# Cpu.net
KiCad netlist of a schematic drawn in Altium Designer
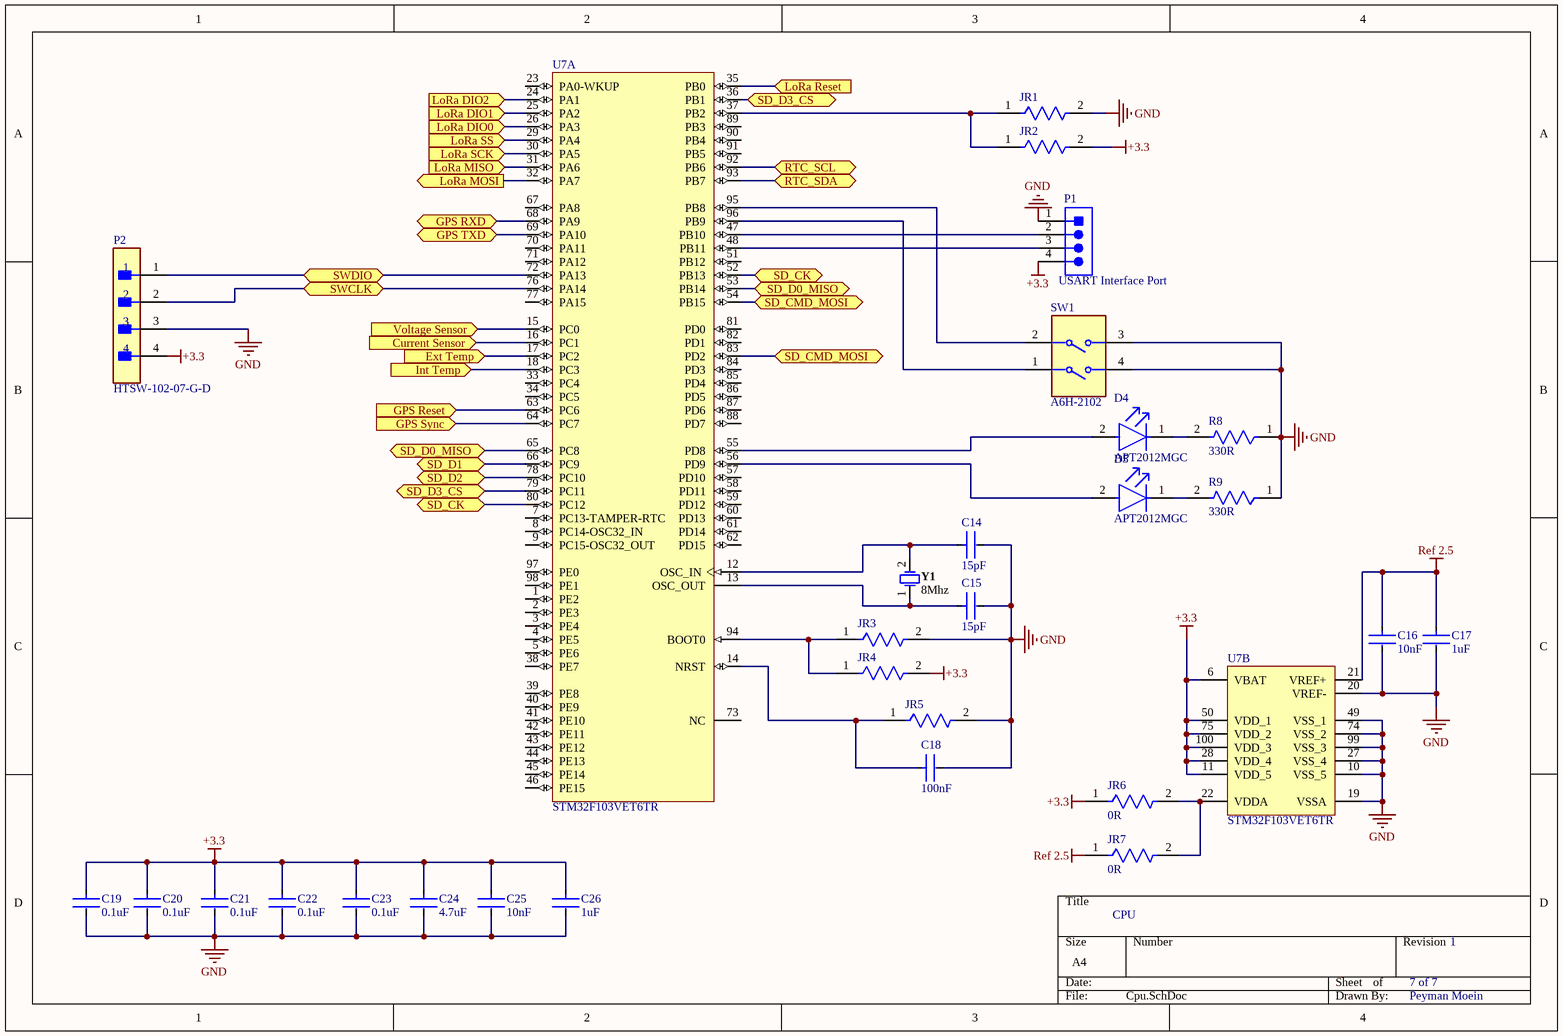
[diagram p0: Cpu.SchDoc]

(export (version "E")
  (design (tool "Eeschema 10.0.6"))
  (components
    (comp (ref "C14")
      (value "15pF")
      (footprint "FP-C0805C-DN-MFG")
      (description "C396747")
      (fields
        (field (name "MANUFACTURER PART NUMBER") "C0805C104K5RACTU")
        (field (name "MANUFACTURER") "KEMET")
      )
      (libsource (lib "Altium Content Vault") (part "b4654b650e69147ec39a6b967a45e02"))
    )
    (comp (ref "C15")
      (value "15pF")
      (footprint "FP-C0805C-DN-MFG")
      (description "C396747")
      (fields
        (field (name "MANUFACTURER PART NUMBER") "C0805C104K5RACTU")
        (field (name "MANUFACTURER") "KEMET")
      )
      (libsource (lib "Altium Content Vault") (part "b4654b650e69147ec39a6b967a45e02"))
    )
    (comp (ref "C16")
      (value "10nF")
      (footprint "FP-C0805C-DN-MFG")
      (description "C188188")
      (fields
        (field (name "MANUFACTURER PART NUMBER") "C0805C104K5RACTU")
        (field (name "MANUFACTURER") "KEMET")
      )
      (libsource (lib "Altium Content Vault") (part "b4654b650e69147ec39a6b967a45e02"))
    )
    (comp (ref "C17")
      (value "1uF")
      (footprint "FP-C0805C-DN-MFG")
      (description "C89190")
      (fields
        (field (name "MANUFACTURER PART NUMBER") "C0805C104K5RACTU")
        (field (name "MANUFACTURER") "KEMET")
      )
      (libsource (lib "Altium Content Vault") (part "b4654b650e69147ec39a6b967a45e02"))
    )
    (comp (ref "C18")
      (value "100nF")
      (footprint "FP-C0805C-DN-MFG")
      (description "C49678")
      (fields
        (field (name "MANUFACTURER PART NUMBER") "C0805C104K5RACTU")
        (field (name "MANUFACTURER") "KEMET")
      )
      (libsource (lib "Altium Content Vault") (part "b4654b650e69147ec39a6b967a45e02"))
    )
    (comp (ref "C19")
      (value "0.1uF")
      (footprint "FP-C0805C-DN-MFG")
      (description "C49678")
      (fields
        (field (name "MANUFACTURER PART NUMBER") "C0805C104K5RACTU")
        (field (name "MANUFACTURER") "KEMET")
      )
      (libsource (lib "Altium Content Vault") (part "b4654b650e69147ec39a6b967a45e02"))
    )
    (comp (ref "C20")
      (value "0.1uF")
      (footprint "FP-C0805C-DN-MFG")
      (description "C49678")
      (fields
        (field (name "MANUFACTURER PART NUMBER") "C0805C104K5RACTU")
        (field (name "MANUFACTURER") "KEMET")
      )
      (libsource (lib "Altium Content Vault") (part "b4654b650e69147ec39a6b967a45e02"))
    )
    (comp (ref "C21")
      (value "0.1uF")
      (footprint "FP-C0805C-DN-MFG")
      (description "C49678")
      (fields
        (field (name "MANUFACTURER PART NUMBER") "C0805C104K5RACTU")
        (field (name "MANUFACTURER") "KEMET")
      )
      (libsource (lib "Altium Content Vault") (part "b4654b650e69147ec39a6b967a45e02"))
    )
    (comp (ref "C22")
      (value "0.1uF")
      (footprint "FP-C0805C-DN-MFG")
      (description "C49678")
      (fields
        (field (name "MANUFACTURER PART NUMBER") "C0805C104K5RACTU")
        (field (name "MANUFACTURER") "KEMET")
      )
      (libsource (lib "Altium Content Vault") (part "b4654b650e69147ec39a6b967a45e02"))
    )
    (comp (ref "C23")
      (value "0.1uF")
      (footprint "FP-C0805C-DN-MFG")
      (description "C49678")
      (fields
        (field (name "MANUFACTURER PART NUMBER") "C0805C104K5RACTU")
        (field (name "MANUFACTURER") "KEMET")
      )
      (libsource (lib "Altium Content Vault") (part "b4654b650e69147ec39a6b967a45e02"))
    )
    (comp (ref "C24")
      (value "4.7uF")
      (footprint "FP-C0805C-DN-MFG")
      (description "C215908")
      (fields
        (field (name "MANUFACTURER PART NUMBER") "C0805C104K5RACTU")
        (field (name "MANUFACTURER") "KEMET")
      )
      (libsource (lib "Altium Content Vault") (part "b4654b650e69147ec39a6b967a45e02"))
    )
    (comp (ref "C25")
      (value "10nF")
      (footprint "FP-C0805C-DN-MFG")
      (description "C188188")
      (fields
        (field (name "MANUFACTURER PART NUMBER") "C0805C104K5RACTU")
        (field (name "MANUFACTURER") "KEMET")
      )
      (libsource (lib "Altium Content Vault") (part "b4654b650e69147ec39a6b967a45e02"))
    )
    (comp (ref "C26")
      (value "1uF")
      (footprint "FP-C0805C-DN-MFG")
      (description "C89190")
      (fields
        (field (name "MANUFACTURER PART NUMBER") "C0805C104K5RACTU")
        (field (name "MANUFACTURER") "KEMET")
      )
      (libsource (lib "Altium Content Vault") (part "b4654b650e69147ec39a6b967a45e02"))
    )
    (comp (ref "D4")
      (value "APT2012MGC")
      (footprint "FP-APT2012MGC-MFG")
      (description "C434432")
      (libsource (lib "Altium Content Vault") (part "8706943c75ba83719d021d2fdc84c58"))
    )
    (comp (ref "D5")
      (value "APT2012MGC")
      (footprint "FP-APT2012MGC-MFG")
      (description "C434432")
      (libsource (lib "Altium Content Vault") (part "8706943c75ba83719d021d2fdc84c58"))
    )
    (comp (ref "JR1")
      (value "0R")
      (footprint "FP-RMCF0805-MFG")
      (description "RES 0 OHM JUMPER 1/8W 0805")
      (libsource (lib "Altium Content Vault") (part "1029c3af85768c4190bb7ad29bc67b5"))
    )
    (comp (ref "JR2")
      (value "0R")
      (footprint "FP-RMCF0805-MFG")
      (libsource (lib "Altium Content Vault") (part "1029c3af85768c4190bb7ad29bc67b5"))
    )
    (comp (ref "JR3")
      (value "0R")
      (footprint "FP-RMCF0805-MFG")
      (description "C25275")
      (libsource (lib "Altium Content Vault") (part "1029c3af85768c4190bb7ad29bc67b5"))
    )
    (comp (ref "JR4")
      (value "0R")
      (footprint "FP-RMCF0805-MFG")
      (description "RES 0 OHM JUMPER 1/8W 0805")
      (libsource (lib "Altium Content Vault") (part "1029c3af85768c4190bb7ad29bc67b5"))
    )
    (comp (ref "JR5")
      (value "NC")
      (footprint "FP-RMCF0805-MFG")
      (description "RES 0 OHM JUMPER 1/8W 0805")
      (libsource (lib "Altium Content Vault") (part "1029c3af85768c4190bb7ad29bc67b5"))
    )
    (comp (ref "JR6")
      (value "0R")
      (footprint "FP-RMCF0805-MFG")
      (description "RES 0 OHM JUMPER 1/8W 0805")
      (libsource (lib "Altium Content Vault") (part "1029c3af85768c4190bb7ad29bc67b5"))
    )
    (comp (ref "JR7")
      (value "0R")
      (footprint "FP-RMCF0805-MFG")
      (description "C25275")
      (libsource (lib "Altium Content Vault") (part "1029c3af85768c4190bb7ad29bc67b5"))
    )
    (comp (ref "P1")
      (value "USART Interface Port")
      (footprint "JST-S4B-XH-A(LF)(SN)_V")
      (description "C157925")
      (libsource (lib "Altium Content Vault") (part "CN-1P-M-R4"))
    )
    (comp (ref "P2")
      (value "HTSW-102-07-G-D")
      (footprint "FP-HTSW-102-07-G-D-MFG")
      (description "C66690")
      (fields
        (field (name "MANUFACTURER") "Samtec")
        (field (name "OCTOPART") "https://octopart.com/htsw-102-07-g-d-samtec-10531767")
      )
      (libsource (lib "Altium Content Vault") (part "299a8cea1bdcbc3624fe62c390fa72c"))
    )
    (comp (ref "R8")
      (value "330R")
      (footprint "FP-CRCW0805-e3-MFG")
      (description "C17630")
      (fields (field (name "TOLERANCE") "1%"))
      (libsource (lib "Altium Content Vault") (part "1029c3af85768c4190bb7ad29bc67b5"))
    )
    (comp (ref "R9")
      (value "330R")
      (footprint "FP-CRCW0805-e3-MFG")
      (description "C17630")
      (fields (field (name "TOLERANCE") "1%"))
      (libsource (lib "Altium Content Vault") (part "1029c3af85768c4190bb7ad29bc67b5"))
    )
    (comp (ref "SW1")
      (value "A6H-2102")
      (footprint "FP-A6H-2102-MFG")
      (description "SWITCH SLIDE DIP SPST 25MA 24V")
      (libsource (lib "Altium Content Vault") (part "070a973bb9dfaf4112c7cb8da95b8f6"))
    )
    (comp (ref "U7")
      (value "STM32F103VET6TR")
      (footprint "STM-LQFP100_L")
      (description "C8308")
      (libsource (lib "Altium Content Vault") (part "MC-ARM-STM32F103XC_D_E-SQ100"))
    )
    (comp (ref "Y1")
      (value "8Mhz")
      (footprint "FOX-FOXSLF080-20")
      (description "C111806")
      (libsource (lib "Altium Content Vault") (part "XTAL-1-2-2"))
    )
  )
  (nets
    (net (code "1") (name "+3.3") (class "Default")
      (node (ref "C19") (pin "1") (pinfunction "1_1") (pintype "passive"))
      (node (ref "C20") (pin "1") (pinfunction "1_1") (pintype "passive"))
      (node (ref "C21") (pin "1") (pinfunction "1_1") (pintype "passive"))
      (node (ref "C22") (pin "1") (pinfunction "1_1") (pintype "passive"))
      (node (ref "C23") (pin "1") (pinfunction "1_1") (pintype "passive"))
      (node (ref "C24") (pin "1") (pinfunction "1_1") (pintype "passive"))
      (node (ref "C25") (pin "1") (pinfunction "1_1") (pintype "passive"))
      (node (ref "C26") (pin "1") (pinfunction "1_1") (pintype "passive"))
      (node (ref "JR2") (pin "2") (pinfunction "2_2") (pintype "passive"))
      (node (ref "JR4") (pin "2") (pinfunction "2_2") (pintype "passive"))
      (node (ref "JR6") (pin "1") (pinfunction "1_1") (pintype "passive"))
      (node (ref "P1") (pin "4") (pinfunction "4_4") (pintype "passive"))
      (node (ref "P2") (pin "4") (pinfunction "4_4") (pintype "passive"))
      (node (ref "U7") (pin "100") (pinfunction "VDD_3_100") (pintype "power_in"))
      (node (ref "U7") (pin "11") (pinfunction "VDD_5_11") (pintype "power_in"))
      (node (ref "U7") (pin "28") (pinfunction "VDD_4_28") (pintype "power_in"))
      (node (ref "U7") (pin "50") (pinfunction "VDD_1_50") (pintype "power_in"))
      (node (ref "U7") (pin "6") (pinfunction "VBAT_6") (pintype "power_in"))
      (node (ref "U7") (pin "75") (pinfunction "VDD_2_75") (pintype "power_in"))
    )
    (net (code "2") (name "/Current Sensor") (class "Default")
      (node (ref "U7") (pin "16") (pinfunction "PC1_16") (pintype "bidirectional"))
    )
    (net (code "3") (name "/Ext Temp") (class "Default")
      (node (ref "U7") (pin "17") (pinfunction "PC2_17") (pintype "bidirectional"))
    )
    (net (code "4") (name "/GPS RXD") (class "Default")
      (node (ref "U7") (pin "68") (pinfunction "PA9_68") (pintype "bidirectional"))
    )
    (net (code "5") (name "/GPS Reset") (class "Default")
      (node (ref "U7") (pin "63") (pinfunction "PC6_63") (pintype "bidirectional"))
    )
    (net (code "6") (name "/GPS Sync") (class "Default")
      (node (ref "U7") (pin "64") (pinfunction "PC7_64") (pintype "bidirectional"))
    )
    (net (code "7") (name "/GPS TXD") (class "Default")
      (node (ref "U7") (pin "69") (pinfunction "PA10_69") (pintype "bidirectional"))
    )
    (net (code "8") (name "/Int Temp") (class "Default")
      (node (ref "U7") (pin "18") (pinfunction "PC3_18") (pintype "bidirectional"))
    )
    (net (code "9") (name "/LoRa DIO0") (class "Default")
      (node (ref "U7") (pin "26") (pinfunction "PA3_26") (pintype "bidirectional"))
    )
    (net (code "10") (name "/LoRa DIO1") (class "Default")
      (node (ref "U7") (pin "25") (pinfunction "PA2_25") (pintype "bidirectional"))
    )
    (net (code "11") (name "/LoRa DIO2") (class "Default")
      (node (ref "U7") (pin "24") (pinfunction "PA1_24") (pintype "bidirectional"))
    )
    (net (code "12") (name "/LoRa MISO") (class "Default")
      (node (ref "U7") (pin "31") (pinfunction "PA6_31") (pintype "bidirectional"))
    )
    (net (code "13") (name "/LoRa MOSI") (class "Default")
      (node (ref "U7") (pin "32") (pinfunction "PA7_32") (pintype "bidirectional"))
    )
    (net (code "14") (name "/LoRa Reset") (class "Default")
      (node (ref "U7") (pin "35") (pinfunction "PB0_35") (pintype "bidirectional"))
    )
    (net (code "15") (name "/LoRa SCK") (class "Default")
      (node (ref "U7") (pin "30") (pinfunction "PA5_30") (pintype "bidirectional"))
    )
    (net (code "16") (name "/LoRa SS") (class "Default")
      (node (ref "U7") (pin "29") (pinfunction "PA4_29") (pintype "bidirectional"))
    )
    (net (code "17") (name "/RTC_SCL") (class "Default")
      (node (ref "U7") (pin "92") (pinfunction "PB6_92") (pintype "bidirectional"))
    )
    (net (code "18") (name "/RTC_SDA") (class "Default")
      (node (ref "U7") (pin "93") (pinfunction "PB7_93") (pintype "bidirectional"))
    )
    (net (code "19") (name "/SD_CK") (class "Default")
      (node (ref "U7") (pin "52") (pinfunction "PB13_52") (pintype "bidirectional"))
      (node (ref "U7") (pin "80") (pinfunction "PC12_80") (pintype "bidirectional"))
    )
    (net (code "20") (name "/SD_CMD_MOSI") (class "Default")
      (node (ref "U7") (pin "54") (pinfunction "PB15_54") (pintype "bidirectional"))
      (node (ref "U7") (pin "83") (pinfunction "PD2_83") (pintype "bidirectional"))
    )
    (net (code "21") (name "/SD_D0_MISO") (class "Default")
      (node (ref "U7") (pin "53") (pinfunction "PB14_53") (pintype "bidirectional"))
      (node (ref "U7") (pin "65") (pinfunction "PC8_65") (pintype "bidirectional"))
    )
    (net (code "22") (name "/SD_D1") (class "Default")
      (node (ref "U7") (pin "66") (pinfunction "PC9_66") (pintype "bidirectional"))
    )
    (net (code "23") (name "/SD_D2") (class "Default")
      (node (ref "U7") (pin "78") (pinfunction "PC10_78") (pintype "bidirectional"))
    )
    (net (code "24") (name "/SD_D3_CS") (class "Default")
      (node (ref "U7") (pin "36") (pinfunction "PB1_36") (pintype "bidirectional"))
      (node (ref "U7") (pin "79") (pinfunction "PC11_79") (pintype "bidirectional"))
    )
    (net (code "25") (name "/SWCLK") (class "Default")
      (node (ref "P2") (pin "2") (pinfunction "2_2") (pintype "passive"))
      (node (ref "U7") (pin "76") (pinfunction "PA14_76") (pintype "bidirectional"))
    )
    (net (code "26") (name "/SWDIO") (class "Default")
      (node (ref "P2") (pin "1") (pinfunction "1_1") (pintype "passive"))
      (node (ref "U7") (pin "72") (pinfunction "PA13_72") (pintype "bidirectional"))
    )
    (net (code "27") (name "/Voltage Sensor") (class "Default")
      (node (ref "U7") (pin "15") (pinfunction "PC0_15") (pintype "bidirectional"))
    )
    (net (code "28") (name "GND") (class "Default")
      (node (ref "C14") (pin "2") (pinfunction "2_2") (pintype "passive"))
      (node (ref "C15") (pin "2") (pinfunction "2_2") (pintype "passive"))
      (node (ref "C16") (pin "2") (pinfunction "2_2") (pintype "passive"))
      (node (ref "C17") (pin "2") (pinfunction "2_2") (pintype "passive"))
      (node (ref "C18") (pin "2") (pinfunction "2_2") (pintype "passive"))
      (node (ref "C19") (pin "2") (pinfunction "2_2") (pintype "passive"))
      (node (ref "C20") (pin "2") (pinfunction "2_2") (pintype "passive"))
      (node (ref "C21") (pin "2") (pinfunction "2_2") (pintype "passive"))
      (node (ref "C22") (pin "2") (pinfunction "2_2") (pintype "passive"))
      (node (ref "C23") (pin "2") (pinfunction "2_2") (pintype "passive"))
      (node (ref "C24") (pin "2") (pinfunction "2_2") (pintype "passive"))
      (node (ref "C25") (pin "2") (pinfunction "2_2") (pintype "passive"))
      (node (ref "C26") (pin "2") (pinfunction "2_2") (pintype "passive"))
      (node (ref "JR1") (pin "2") (pinfunction "2_2") (pintype "passive"))
      (node (ref "JR3") (pin "2") (pinfunction "2_2") (pintype "passive"))
      (node (ref "JR5") (pin "2") (pinfunction "2_2") (pintype "passive"))
      (node (ref "P1") (pin "1") (pinfunction "1_1") (pintype "passive"))
      (node (ref "P2") (pin "3") (pinfunction "3_3") (pintype "passive"))
      (node (ref "R8") (pin "1") (pinfunction "1_1") (pintype "passive"))
      (node (ref "R9") (pin "1") (pinfunction "1_1") (pintype "passive"))
      (node (ref "SW1") (pin "3") (pinfunction "3_3") (pintype "passive"))
      (node (ref "SW1") (pin "4") (pinfunction "4_4") (pintype "passive"))
      (node (ref "U7") (pin "10") (pinfunction "VSS_5_10") (pintype "power_in"))
      (node (ref "U7") (pin "19") (pinfunction "VSSA_19") (pintype "power_in"))
      (node (ref "U7") (pin "20") (pinfunction "VREF-_20") (pintype "power_in"))
      (node (ref "U7") (pin "27") (pinfunction "VSS_4_27") (pintype "power_in"))
      (node (ref "U7") (pin "49") (pinfunction "VSS_1_49") (pintype "power_in"))
      (node (ref "U7") (pin "74") (pinfunction "VSS_2_74") (pintype "power_in"))
      (node (ref "U7") (pin "99") (pinfunction "VSS_3_99") (pintype "power_in"))
    )
    (net (code "29") (name "Net-(D4-A)") (class "Default")
      (node (ref "D4") (pin "2") (pinfunction "A_2") (pintype "passive"))
      (node (ref "U7") (pin "55") (pinfunction "PD8_55") (pintype "bidirectional"))
    )
    (net (code "30") (name "Net-(D4-C)") (class "Default")
      (node (ref "D4") (pin "1") (pinfunction "C_1") (pintype "passive"))
      (node (ref "R8") (pin "2") (pinfunction "2_2") (pintype "passive"))
    )
    (net (code "31") (name "Net-(D5-A)") (class "Default")
      (node (ref "D5") (pin "2") (pinfunction "A_2") (pintype "passive"))
      (node (ref "U7") (pin "56") (pinfunction "PD9_56") (pintype "bidirectional"))
    )
    (net (code "32") (name "Net-(D5-C)") (class "Default")
      (node (ref "D5") (pin "1") (pinfunction "C_1") (pintype "passive"))
      (node (ref "R9") (pin "2") (pinfunction "2_2") (pintype "passive"))
    )
    (net (code "33") (name "Net-(U7A-BOOT0)") (class "Default")
      (node (ref "JR3") (pin "1") (pinfunction "1_1") (pintype "passive"))
      (node (ref "JR4") (pin "1") (pinfunction "1_1") (pintype "passive"))
      (node (ref "U7") (pin "94") (pinfunction "BOOT0_94") (pintype "input"))
    )
    (net (code "34") (name "Net-(U7A-NRST)") (class "Default")
      (node (ref "C18") (pin "1") (pinfunction "1_1") (pintype "passive"))
      (node (ref "JR5") (pin "1") (pinfunction "1_1") (pintype "passive"))
      (node (ref "U7") (pin "14") (pinfunction "NRST_14") (pintype "bidirectional"))
    )
    (net (code "35") (name "Net-(U7A-OSC_IN)") (class "Default")
      (node (ref "C14") (pin "1") (pinfunction "1_1") (pintype "passive"))
      (node (ref "U7") (pin "12") (pinfunction "OSC_IN_12") (pintype "input"))
      (node (ref "Y1") (pin "2") (pinfunction "2_2") (pintype "passive"))
    )
    (net (code "36") (name "Net-(U7A-OSC_OUT)") (class "Default")
      (node (ref "C15") (pin "1") (pinfunction "1_1") (pintype "passive"))
      (node (ref "U7") (pin "13") (pinfunction "OSC_OUT_13") (pintype "passive"))
      (node (ref "Y1") (pin "1") (pinfunction "1_1") (pintype "passive"))
    )
    (net (code "37") (name "Net-(U7A-PB2)") (class "Default")
      (node (ref "JR1") (pin "1") (pinfunction "1_1") (pintype "passive"))
      (node (ref "JR2") (pin "1") (pinfunction "1_1") (pintype "passive"))
      (node (ref "U7") (pin "37") (pinfunction "PB2_37") (pintype "bidirectional"))
    )
    (net (code "38") (name "Net-(U7A-PB8)") (class "Default")
      (node (ref "SW1") (pin "2") (pinfunction "2_2") (pintype "passive"))
      (node (ref "U7") (pin "95") (pinfunction "PB8_95") (pintype "bidirectional"))
    )
    (net (code "39") (name "Net-(U7A-PB9)") (class "Default")
      (node (ref "SW1") (pin "1") (pinfunction "1_1") (pintype "passive"))
      (node (ref "U7") (pin "96") (pinfunction "PB9_96") (pintype "bidirectional"))
    )
    (net (code "40") (name "Net-(U7A-PB10)") (class "Default")
      (node (ref "P1") (pin "2") (pinfunction "2_2") (pintype "passive"))
      (node (ref "U7") (pin "47") (pinfunction "PB10_47") (pintype "bidirectional"))
    )
    (net (code "41") (name "Net-(U7A-PB11)") (class "Default")
      (node (ref "P1") (pin "3") (pinfunction "3_3") (pintype "passive"))
      (node (ref "U7") (pin "48") (pinfunction "PB11_48") (pintype "bidirectional"))
    )
    (net (code "42") (name "Net-(U7B-VDDA)") (class "Default")
      (node (ref "JR6") (pin "2") (pinfunction "2_2") (pintype "passive"))
      (node (ref "JR7") (pin "2") (pinfunction "2_2") (pintype "passive"))
      (node (ref "U7") (pin "22") (pinfunction "VDDA_22") (pintype "power_in"))
    )
    (net (code "43") (name "Ref 2.5") (class "Default")
      (node (ref "C16") (pin "1") (pinfunction "1_1") (pintype "passive"))
      (node (ref "C17") (pin "1") (pinfunction "1_1") (pintype "passive"))
      (node (ref "JR7") (pin "1") (pinfunction "1_1") (pintype "passive"))
      (node (ref "U7") (pin "21") (pinfunction "VREF+_21") (pintype "power_in"))
    )
    (net (code "44") (name "unconnected-(U7A-NC-Pad73)") (class "Default")
      (node (ref "U7") (pin "73") (pinfunction "NC_73") (pintype "passive"))
    )
    (net (code "45") (name "unconnected-(U7A-PA0-WKUP-Pad23)") (class "Default")
      (node (ref "U7") (pin "23") (pinfunction "PA0-WKUP_23") (pintype "bidirectional"))
    )
    (net (code "46") (name "unconnected-(U7A-PA8-Pad67)") (class "Default")
      (node (ref "U7") (pin "67") (pinfunction "PA8_67") (pintype "bidirectional"))
    )
    (net (code "47") (name "unconnected-(U7A-PA11-Pad70)") (class "Default")
      (node (ref "U7") (pin "70") (pinfunction "PA11_70") (pintype "bidirectional"))
    )
    (net (code "48") (name "unconnected-(U7A-PA12-Pad71)") (class "Default")
      (node (ref "U7") (pin "71") (pinfunction "PA12_71") (pintype "bidirectional"))
    )
    (net (code "49") (name "unconnected-(U7A-PA15-Pad77)") (class "Default")
      (node (ref "U7") (pin "77") (pinfunction "PA15_77") (pintype "bidirectional"))
    )
    (net (code "50") (name "unconnected-(U7A-PB3-Pad89)") (class "Default")
      (node (ref "U7") (pin "89") (pinfunction "PB3_89") (pintype "bidirectional"))
    )
    (net (code "51") (name "unconnected-(U7A-PB4-Pad90)") (class "Default")
      (node (ref "U7") (pin "90") (pinfunction "PB4_90") (pintype "bidirectional"))
    )
    (net (code "52") (name "unconnected-(U7A-PB5-Pad91)") (class "Default")
      (node (ref "U7") (pin "91") (pinfunction "PB5_91") (pintype "bidirectional"))
    )
    (net (code "53") (name "unconnected-(U7A-PB12-Pad51)") (class "Default")
      (node (ref "U7") (pin "51") (pinfunction "PB12_51") (pintype "bidirectional"))
    )
    (net (code "54") (name "unconnected-(U7A-PC4-Pad33)") (class "Default")
      (node (ref "U7") (pin "33") (pinfunction "PC4_33") (pintype "bidirectional"))
    )
    (net (code "55") (name "unconnected-(U7A-PC5-Pad34)") (class "Default")
      (node (ref "U7") (pin "34") (pinfunction "PC5_34") (pintype "bidirectional"))
    )
    (net (code "56") (name "unconnected-(U7A-PC13-TAMPER-RTC-Pad7)") (class "Default")
      (node (ref "U7") (pin "7") (pinfunction "PC13-TAMPER-RTC_7") (pintype "bidirectional"))
    )
    (net (code "57") (name "unconnected-(U7A-PC14-OSC32_IN-Pad8)") (class "Default")
      (node (ref "U7") (pin "8") (pinfunction "PC14-OSC32_IN_8") (pintype "bidirectional"))
    )
    (net (code "58") (name "unconnected-(U7A-PC15-OSC32_OUT-Pad9)") (class "Default")
      (node (ref "U7") (pin "9") (pinfunction "PC15-OSC32_OUT_9") (pintype "bidirectional"))
    )
    (net (code "59") (name "unconnected-(U7A-PD0-Pad81)") (class "Default")
      (node (ref "U7") (pin "81") (pinfunction "PD0_81") (pintype "bidirectional"))
    )
    (net (code "60") (name "unconnected-(U7A-PD1-Pad82)") (class "Default")
      (node (ref "U7") (pin "82") (pinfunction "PD1_82") (pintype "bidirectional"))
    )
    (net (code "61") (name "unconnected-(U7A-PD3-Pad84)") (class "Default")
      (node (ref "U7") (pin "84") (pinfunction "PD3_84") (pintype "bidirectional"))
    )
    (net (code "62") (name "unconnected-(U7A-PD4-Pad85)") (class "Default")
      (node (ref "U7") (pin "85") (pinfunction "PD4_85") (pintype "bidirectional"))
    )
    (net (code "63") (name "unconnected-(U7A-PD5-Pad86)") (class "Default")
      (node (ref "U7") (pin "86") (pinfunction "PD5_86") (pintype "bidirectional"))
    )
    (net (code "64") (name "unconnected-(U7A-PD6-Pad87)") (class "Default")
      (node (ref "U7") (pin "87") (pinfunction "PD6_87") (pintype "bidirectional"))
    )
    (net (code "65") (name "unconnected-(U7A-PD7-Pad88)") (class "Default")
      (node (ref "U7") (pin "88") (pinfunction "PD7_88") (pintype "bidirectional"))
    )
    (net (code "66") (name "unconnected-(U7A-PD10-Pad57)") (class "Default")
      (node (ref "U7") (pin "57") (pinfunction "PD10_57") (pintype "bidirectional"))
    )
    (net (code "67") (name "unconnected-(U7A-PD11-Pad58)") (class "Default")
      (node (ref "U7") (pin "58") (pinfunction "PD11_58") (pintype "bidirectional"))
    )
    (net (code "68") (name "unconnected-(U7A-PD12-Pad59)") (class "Default")
      (node (ref "U7") (pin "59") (pinfunction "PD12_59") (pintype "bidirectional"))
    )
    (net (code "69") (name "unconnected-(U7A-PD13-Pad60)") (class "Default")
      (node (ref "U7") (pin "60") (pinfunction "PD13_60") (pintype "bidirectional"))
    )
    (net (code "70") (name "unconnected-(U7A-PD14-Pad61)") (class "Default")
      (node (ref "U7") (pin "61") (pinfunction "PD14_61") (pintype "bidirectional"))
    )
    (net (code "71") (name "unconnected-(U7A-PD15-Pad62)") (class "Default")
      (node (ref "U7") (pin "62") (pinfunction "PD15_62") (pintype "bidirectional"))
    )
    (net (code "72") (name "unconnected-(U7A-PE0-Pad97)") (class "Default")
      (node (ref "U7") (pin "97") (pinfunction "PE0_97") (pintype "bidirectional"))
    )
    (net (code "73") (name "unconnected-(U7A-PE1-Pad98)") (class "Default")
      (node (ref "U7") (pin "98") (pinfunction "PE1_98") (pintype "bidirectional"))
    )
    (net (code "74") (name "unconnected-(U7A-PE2-Pad1)") (class "Default")
      (node (ref "U7") (pin "1") (pinfunction "PE2_1") (pintype "bidirectional"))
    )
    (net (code "75") (name "unconnected-(U7A-PE3-Pad2)") (class "Default")
      (node (ref "U7") (pin "2") (pinfunction "PE3_2") (pintype "bidirectional"))
    )
    (net (code "76") (name "unconnected-(U7A-PE4-Pad3)") (class "Default")
      (node (ref "U7") (pin "3") (pinfunction "PE4_3") (pintype "bidirectional"))
    )
    (net (code "77") (name "unconnected-(U7A-PE5-Pad4)") (class "Default")
      (node (ref "U7") (pin "4") (pinfunction "PE5_4") (pintype "bidirectional"))
    )
    (net (code "78") (name "unconnected-(U7A-PE6-Pad5)") (class "Default")
      (node (ref "U7") (pin "5") (pinfunction "PE6_5") (pintype "bidirectional"))
    )
    (net (code "79") (name "unconnected-(U7A-PE7-Pad38)") (class "Default")
      (node (ref "U7") (pin "38") (pinfunction "PE7_38") (pintype "bidirectional"))
    )
    (net (code "80") (name "unconnected-(U7A-PE8-Pad39)") (class "Default")
      (node (ref "U7") (pin "39") (pinfunction "PE8_39") (pintype "bidirectional"))
    )
    (net (code "81") (name "unconnected-(U7A-PE9-Pad40)") (class "Default")
      (node (ref "U7") (pin "40") (pinfunction "PE9_40") (pintype "bidirectional"))
    )
    (net (code "82") (name "unconnected-(U7A-PE10-Pad41)") (class "Default")
      (node (ref "U7") (pin "41") (pinfunction "PE10_41") (pintype "bidirectional"))
    )
    (net (code "83") (name "unconnected-(U7A-PE11-Pad42)") (class "Default")
      (node (ref "U7") (pin "42") (pinfunction "PE11_42") (pintype "bidirectional"))
    )
    (net (code "84") (name "unconnected-(U7A-PE12-Pad43)") (class "Default")
      (node (ref "U7") (pin "43") (pinfunction "PE12_43") (pintype "bidirectional"))
    )
    (net (code "85") (name "unconnected-(U7A-PE13-Pad44)") (class "Default")
      (node (ref "U7") (pin "44") (pinfunction "PE13_44") (pintype "bidirectional"))
    )
    (net (code "86") (name "unconnected-(U7A-PE14-Pad45)") (class "Default")
      (node (ref "U7") (pin "45") (pinfunction "PE14_45") (pintype "bidirectional"))
    )
    (net (code "87") (name "unconnected-(U7A-PE15-Pad46)") (class "Default")
      (node (ref "U7") (pin "46") (pinfunction "PE15_46") (pintype "bidirectional"))
    )
  )
)
